# 3_3_buck.net
KiCad netlist of a schematic drawn in Altium Designer
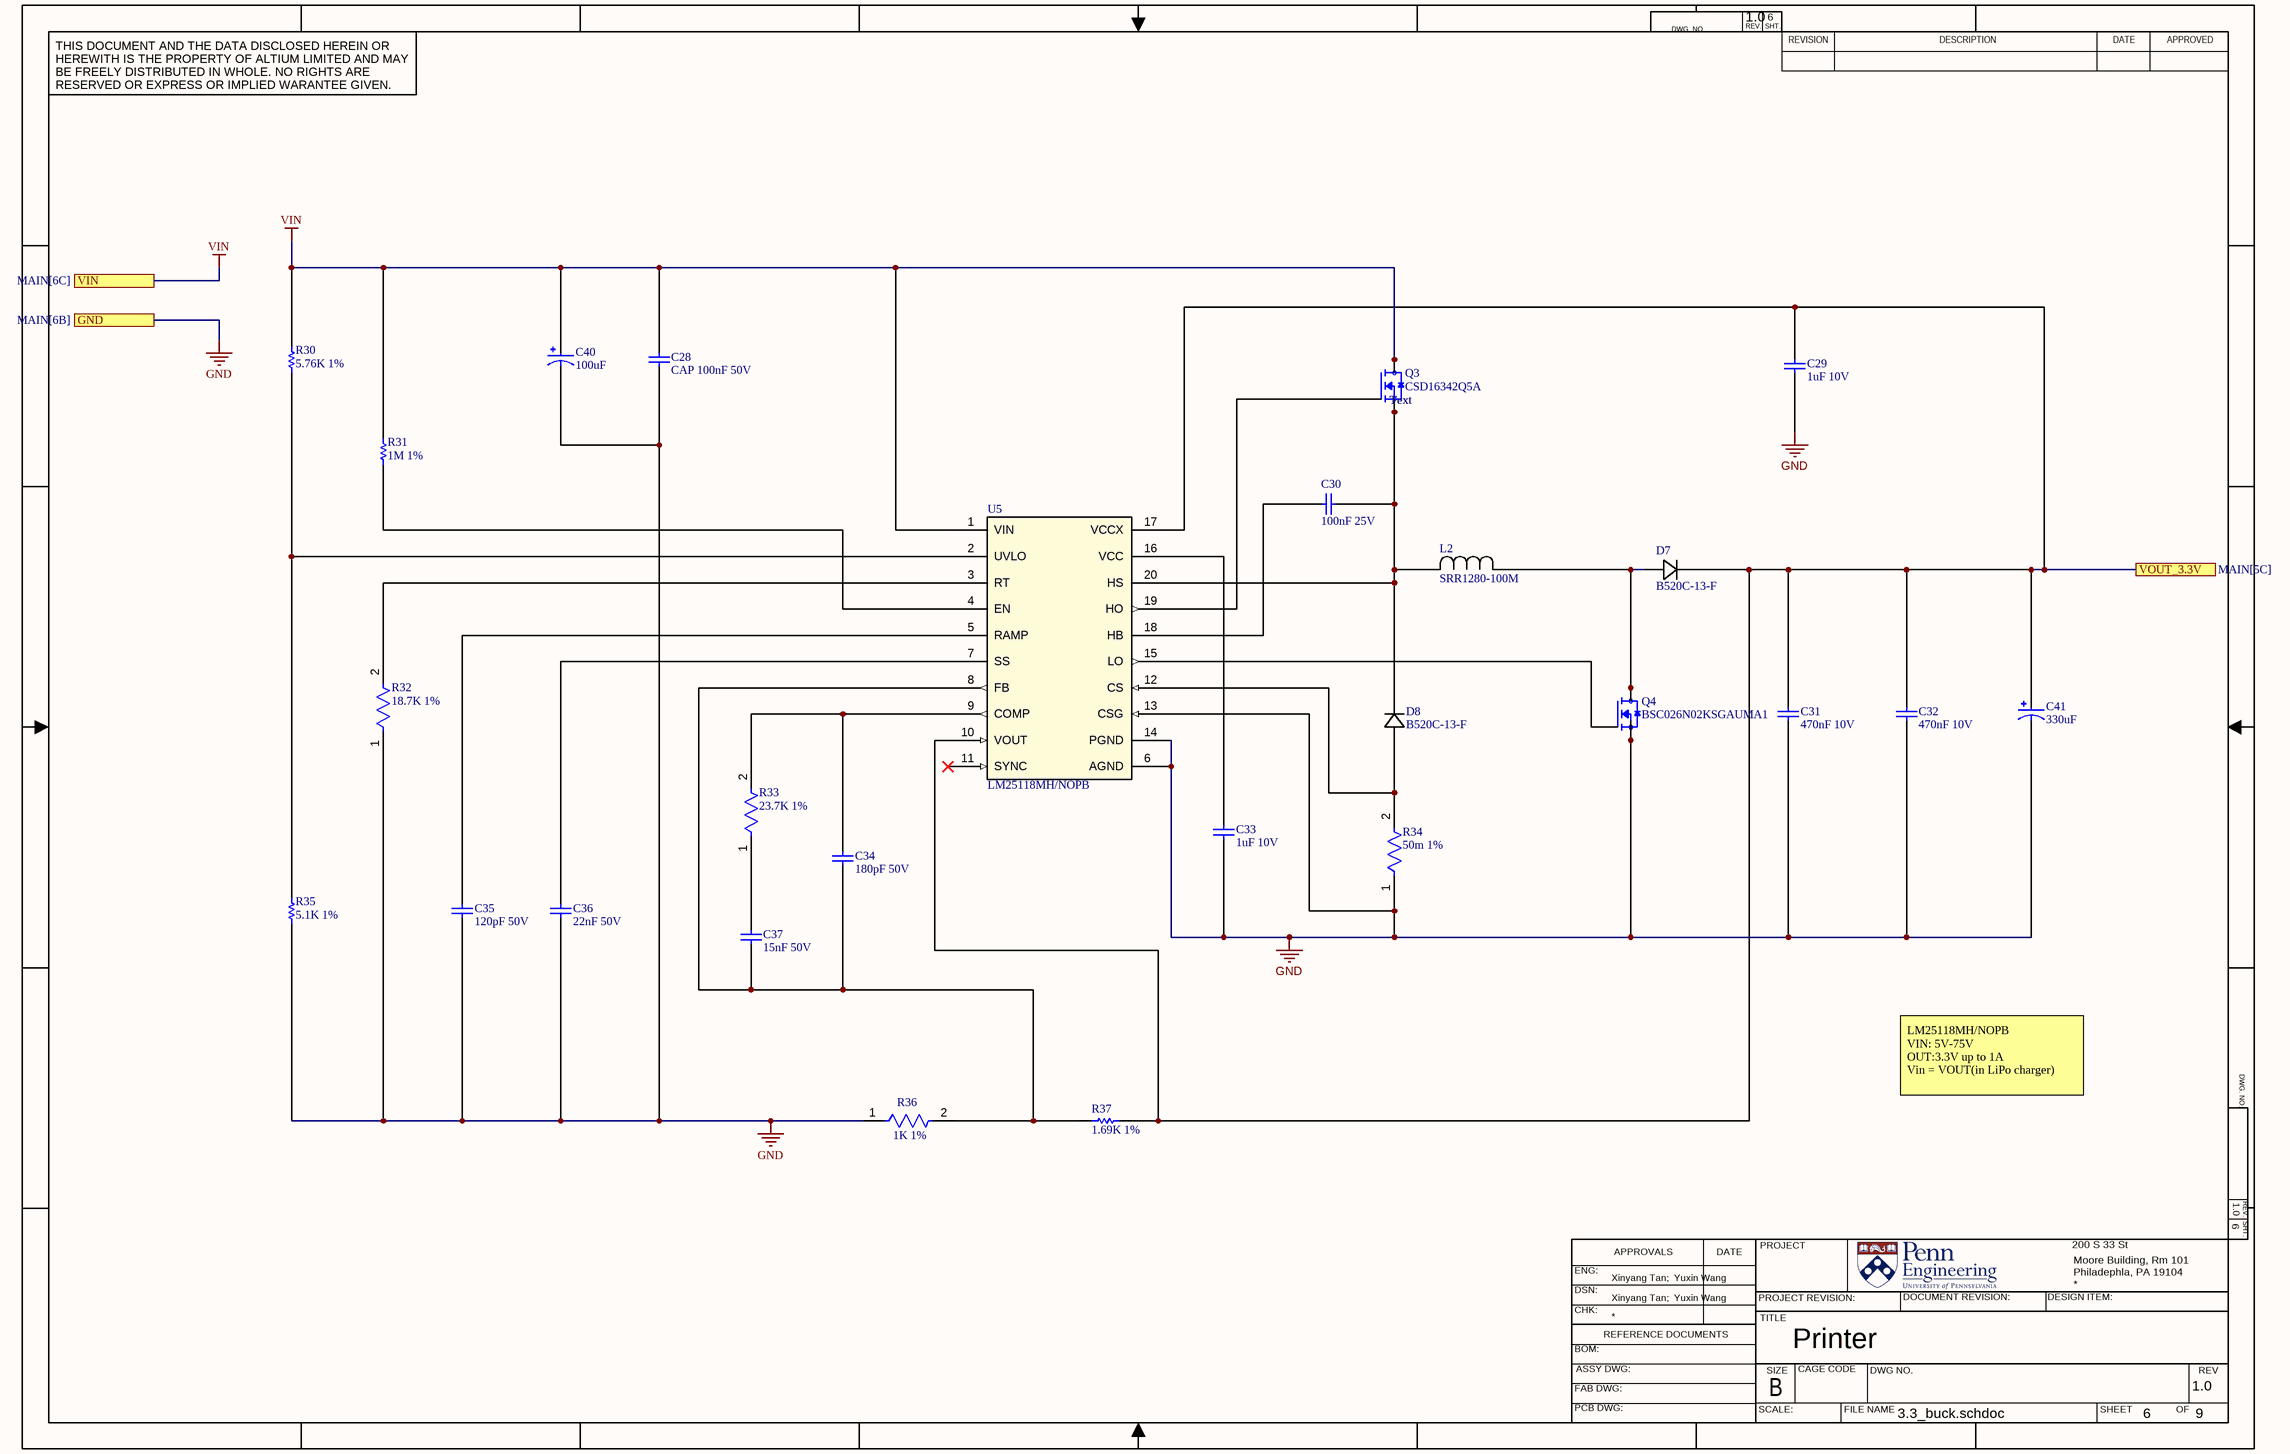
[diagram p0: 3.3_buck.schdoc]

(export (version "E")
  (design (tool "Eeschema 10.0.6"))
  (components
    (comp (ref "C28")
      (value "CAP 100nF 50V")
      (footprint "CAPC0805(2012)100_L")
      (description "CAP 100nF 50V ±5% 0805 (2012 Metric) Thickness 1mm SMD")
      (fields (field (name "TOLERANCE") "Â±5%"))
      (libsource (lib "Altium Content Vault") (part "CAP"))
    )
    (comp (ref "C29")
      (value "1uF 10V")
      (footprint "CAPC1608X90X35ML15T15")
      (fields (field (name "MANUFACTURER") "Kemet") (field (name "PART NUMBER") "C0603C105K8RACTU"))
      (libsource (lib "Altium Content Vault") (part "CAP"))
    )
    (comp (ref "C30")
      (value "100nF 25V")
      (footprint "CAPC0805(2012)75_M")
      (description "CAP 100nF 25V ±20% 0805 (2012 Metric) Thickness 0.75mm SMD")
      (fields (field (name "TOLERANCE") "Â±20%"))
      (libsource (lib "Altium Content Vault") (part "CAP"))
    )
    (comp (ref "C31")
      (value "470nF 10V")
      (footprint "CAPC0402(1005)60_M")
      (description "CAP 470nF 10V -20% to +80% 0402 (1005 Metric) Thickness 0.6mm SMD")
      (fields (field (name "TOLERANCE") "-20% to +80%"))
      (libsource (lib "Altium Content Vault") (part "CAP"))
    )
    (comp (ref "C32")
      (value "470nF 10V")
      (footprint "CAPC0402(1005)60_M")
      (description "CAP 470nF 10V -20% to +80% 0402 (1005 Metric) Thickness 0.6mm SMD")
      (fields (field (name "TOLERANCE") "-20% to +80%"))
      (libsource (lib "Altium Content Vault") (part "CAP"))
    )
    (comp (ref "C33")
      (value "1uF 10V")
      (footprint "CAPC1608X90X35ML15T15")
      (fields (field (name "MANUFACTURER") "Kemet") (field (name "PART NUMBER") "C0603C105K8RACTU"))
      (libsource (lib "Altium Content Vault") (part "CAP"))
    )
    (comp (ref "C34")
      (value "180pF 50V")
      (footprint "CAPC0805(2012)100_L")
      (description "CAP 180pF 50V ±20% 0805 (2012 Metric) Thickness 1mm SMD")
      (fields (field (name "TOLERANCE") "Â±20%"))
      (libsource (lib "Altium Content Vault") (part "CAP"))
    )
    (comp (ref "C35")
      (value "120pF 50V")
      (footprint "CAPC0805(2012)75_L")
      (description "CAP 120pF 50V ±10% 0805 (2012 Metric) Thickness 0.75mm SMD")
      (fields (field (name "TOLERANCE") "Â±10%"))
      (libsource (lib "Altium Content Vault") (part "CAP"))
    )
    (comp (ref "C36")
      (value "22nF 50V")
      (footprint "CAPC0805(2012)75_N")
      (description "CAP 22nF 50V ±20% 0805 (2012 Metric) Thickness 0.75mm SMD")
      (fields (field (name "TOLERANCE") "Â±20%"))
      (libsource (lib "Altium Content Vault") (part "CAP"))
    )
    (comp (ref "C37")
      (value "15nF 50V")
      (footprint "CAPC0805(2012)75_N")
      (description "CAP 15nF 50V ±20% 0805 (2012 Metric) Thickness 0.75mm SMD")
      (fields (field (name "TOLERANCE") "Â±20%"))
      (libsource (lib "Altium Content Vault") (part "CAP"))
    )
    (comp (ref "C40")
      (value "100uF")
      (footprint "CAP_593D-D_VSS")
      (description "No Description Available")
      (fields
        (field (name "MANUFACTURER_PART_NUMBER") "593D107X0010D2TE3")
        (field (name "COPYRIGHT") "Copyright (C) 2022 Ultra Librarian. All rights reserved.")
      )
      (libsource (lib "Schematics") (part "593D107X0010D2TE3"))
    )
    (comp (ref "C41")
      (value "330uF")
      (footprint "CHEMI-F80")
      (description "No Description Available")
      (fields
        (field (name "MANUFACTURER_PART_NUMBER") "APXE6R3ARA331MF80G")
        (field (name "COPYRIGHT") "Copyright (C) 2022 Ultra Librarian. All rights reserved.")
      )
      (libsource (lib "Schematics") (part "APXE6R3ARA331MF80G"))
    )
    (comp (ref "D7")
      (value "B520C-13-F")
      (footprint "SMC_DIO")
      (description "No Description Available")
      (fields (field (name "COPYRIGHT") "Copyright (C) 2022 Ultra Librarian. All rights reserved."))
      (libsource (lib "Schematics") (part "B520C-13-F"))
    )
    (comp (ref "D8")
      (value "B520C-13-F")
      (footprint "SMC_DIO")
      (description "No Description Available")
      (fields (field (name "COPYRIGHT") "Copyright (C) 2022 Ultra Librarian. All rights reserved."))
      (libsource (lib "Schematics") (part "B520C-13-F"))
    )
    (comp (ref "L2")
      (value "SRR1280-100M")
      (footprint "IND_BOURNS_SRR1280")
      (description "No Description Available")
      (fields (field (name "COPYRIGHT") "Copyright (C) 2022 Ultra Librarian. All rights reserved."))
      (libsource (lib "Schematics") (part "SRR1280-100M"))
    )
    (comp (ref "Q3")
      (value "CSD16342Q5A")
      (footprint "DQJ8_TEX")
      (description "No Description Available")
      (fields (field (name "COPYRIGHT") "Copyright (C) 2022 Ultra Librarian. All rights reserved."))
      (libsource (lib "Schematics") (part "CSD16342Q5A"))
    )
    (comp (ref "Q4")
      (value "BSC026N02KSGAUMA1")
      (footprint "PG-TDSON-8_BSC026N02KSGAUMA1_INF")
      (description "No Description Available")
      (fields (field (name "COPYRIGHT") "Copyright (C) 2022 Ultra Librarian. All rights reserved."))
      (libsource (lib "Schematics") (part "BSC026N02KSGAUMA1"))
    )
    (comp (ref "R30")
      (value "5.76K 1%")
      (footprint "RESC1608X55X25ML10T15")
      (fields (field (name "PART NUMBER") "RC0603FR-075K76L") (field (name "MANUFACTURER") "Yageo"))
      (libsource (lib "Altium Content Vault") (part "RES"))
    )
    (comp (ref "R31")
      (value "1M 1%")
      (footprint "RESC1608X55X25LL10T15")
      (description "Chip Resistor, 1 MOhm, +/- 1%, 100 mW, -55 to 155 degC, 0603 (1608 Metric), RoHS, Tape and Reel")
      (fields (field (name "TOLERANCE") "20%"))
      (libsource (lib "Altium Content Vault") (part "RES-2"))
    )
    (comp (ref "R32")
      (value "18.7K 1%")
      (footprint "FP-RT0805-MFG")
      (description "RES SMD 18.7K OHM 1% 1/8W 0805")
      (fields
        (field (name "OCTOPART") "https://octopart.com/rt0805fre0718k7l-yageo-1462871")
        (field (name "TOLERANCE") "0.0001")
      )
      (libsource (lib "Altium Content Vault") (part "1029c3af85768c4190bb7ad29bc67b5"))
    )
    (comp (ref "R33")
      (value "23.7K 1%")
      (footprint "FP-AC0402-MFG")
      (description "RES SMD 23.7K OHM 1% 1/16W 0402")
      (fields
        (field (name "OCTOPART") "https://octopart.com/ac0402fr-0723k7l-yageo-71366670")
        (field (name "MANUFACTURER PART NUMBER") "AC0402FR-0723K7L")
      )
      (libsource (lib "Altium Content Vault") (part "1029c3af85768c4190bb7ad29bc67b5"))
    )
    (comp (ref "R34")
      (value "50m 1%")
      (footprint "FP-CSR1206-IPC_A")
      (description "General Purpose Thick Film Chip Resistor, 1206, 50mΩ, 1%, 100ppm/°C, 0.5W")
      (fields (field (name "TOLERANCE") "1%"))
      (libsource (lib "Altium Content Vault") (part "1029c3af85768c4190bb7ad29bc67b5"))
    )
    (comp (ref "R35")
      (value "5.1K 1%")
      (footprint "RESC1608X55X25ML10T15")
      (fields (field (name "MANUFACTURER") "Yageo") (field (name "PART NUMBER") "RC0603FR-075K1L"))
      (libsource (lib "Altium Content Vault") (part "RES"))
    )
    (comp (ref "R36")
      (value "1K 1%")
      (footprint "FP-RC0603-0_55-IPC_C")
      (description "RES 1K OHM 1% 1/10W 0603")
      (fields (field (name "TOLERANCE") "1%"))
      (libsource (lib "Altium Content Vault") (part "1029c3af85768c4190bb7ad29bc67b5"))
    )
    (comp (ref "R37")
      (value "1.69K 1%")
      (footprint "RESC1608X55X25NL10T15")
      (fields (field (name "MANUFACTURER") "Yageo") (field (name "PART NUMBER") "RC0603FR-071K69L"))
      (libsource (lib "Altium Content Vault") (part "RES"))
    )
    (comp (ref "U5")
      (value "LM25118MH/NOPB")
      (footprint "MXA20A")
      (description "No Description Available")
      (fields (field (name "COPYRIGHT") "Copyright (C) 2022 Ultra Librarian. All rights reserved."))
      (libsource (lib "Schematics") (part "LM25118MH/NOPB"))
    )
  )
  (nets
    (net (code "1") (name "/VOUT_3.3V") (class "Default")
      (node (ref "C29") (pin "2") (pinfunction "2_2") (pintype "passive"))
      (node (ref "C31") (pin "2") (pinfunction "2_2") (pintype "passive"))
      (node (ref "C32") (pin "2") (pinfunction "2_2") (pintype "passive"))
      (node (ref "C41") (pin "1") (pinfunction "1_1") (pintype "passive"))
      (node (ref "D7") (pin "1") (pinfunction "1_1") (pintype "passive"))
      (node (ref "R37") (pin "2") (pinfunction "2_2") (pintype "passive"))
      (node (ref "U5") (pin "10") (pinfunction "VOUT_10") (pintype "input"))
      (node (ref "U5") (pin "17") (pinfunction "VCCX_17") (pintype "power_in"))
    )
    (net (code "2") (name "GND") (class "Default")
      (node (ref "C28") (pin "1") (pinfunction "1_1") (pintype "passive"))
      (node (ref "C29") (pin "1") (pinfunction "1_1") (pintype "passive"))
      (node (ref "C31") (pin "1") (pinfunction "1_1") (pintype "passive"))
      (node (ref "C32") (pin "1") (pinfunction "1_1") (pintype "passive"))
      (node (ref "C33") (pin "1") (pinfunction "1_1") (pintype "passive"))
      (node (ref "C35") (pin "1") (pinfunction "1_1") (pintype "passive"))
      (node (ref "C36") (pin "1") (pinfunction "1_1") (pintype "passive"))
      (node (ref "C40") (pin "2") (pinfunction "2_2") (pintype "passive"))
      (node (ref "C41") (pin "2") (pinfunction "2_2") (pintype "passive"))
      (node (ref "Q4") (pin "2") (pinfunction "S_2") (pintype "passive"))
      (node (ref "Q4") (pin "3") (pinfunction "S_3") (pintype "passive"))
      (node (ref "R32") (pin "1") (pinfunction "1_1") (pintype "passive"))
      (node (ref "R34") (pin "1") (pinfunction "1_1") (pintype "passive"))
      (node (ref "R35") (pin "1") (pinfunction "1_1") (pintype "passive"))
      (node (ref "R36") (pin "1") (pinfunction "1_1") (pintype "passive"))
      (node (ref "U5") (pin "13") (pinfunction "CSG_13") (pintype "input"))
      (node (ref "U5") (pin "14") (pinfunction "PGND_14") (pintype "power_in"))
      (node (ref "U5") (pin "6") (pinfunction "AGND_6") (pintype "power_in"))
    )
    (net (code "3") (name "Net-(C37-Pad2)") (class "Default")
      (node (ref "C37") (pin "2") (pinfunction "2_2") (pintype "passive"))
      (node (ref "R33") (pin "1") (pinfunction "1_1") (pintype "passive"))
    )
    (net (code "4") (name "Net-(D7-Pad2)") (class "Default")
      (node (ref "D7") (pin "2") (pinfunction "2_2") (pintype "passive"))
      (node (ref "L2") (pin "1") (pinfunction "1_1") (pintype "passive"))
      (node (ref "Q4") (pin "5") (pinfunction "D_5") (pintype "passive"))
      (node (ref "Q4") (pin "6") (pinfunction "D_6") (pintype "passive"))
      (node (ref "Q4") (pin "7") (pinfunction "D_7") (pintype "passive"))
      (node (ref "Q4") (pin "8") (pinfunction "D_8") (pintype "passive"))
    )
    (net (code "5") (name "Net-(Q3-G)") (class "Default")
      (node (ref "Q3") (pin "4") (pinfunction "G_4") (pintype "passive"))
      (node (ref "U5") (pin "19") (pinfunction "HO_19") (pintype "output"))
    )
    (net (code "6") (name "Net-(Q4-G)") (class "Default")
      (node (ref "Q4") (pin "4") (pinfunction "G_4") (pintype "passive"))
      (node (ref "U5") (pin "15") (pinfunction "LO_15") (pintype "output"))
    )
    (net (code "7") (name "Net-(U5-COMP)") (class "Default")
      (node (ref "C34") (pin "2") (pinfunction "2_2") (pintype "passive"))
      (node (ref "R33") (pin "2") (pinfunction "2_2") (pintype "passive"))
      (node (ref "U5") (pin "9") (pinfunction "COMP_9") (pintype "output"))
    )
    (net (code "8") (name "Net-(U5-CS)") (class "Default")
      (node (ref "D8") (pin "2") (pinfunction "2_2") (pintype "passive"))
      (node (ref "R34") (pin "2") (pinfunction "2_2") (pintype "passive"))
      (node (ref "U5") (pin "12") (pinfunction "CS_12") (pintype "input"))
    )
    (net (code "9") (name "Net-(U5-EN)") (class "Default")
      (node (ref "R31") (pin "1") (pinfunction "1_1") (pintype "passive"))
      (node (ref "U5") (pin "4") (pinfunction "EN_4") (pintype "passive"))
    )
    (net (code "10") (name "Net-(U5-FB)") (class "Default")
      (node (ref "C34") (pin "1") (pinfunction "1_1") (pintype "passive"))
      (node (ref "C37") (pin "1") (pinfunction "1_1") (pintype "passive"))
      (node (ref "R36") (pin "2") (pinfunction "2_2") (pintype "passive"))
      (node (ref "R37") (pin "1") (pinfunction "1_1") (pintype "passive"))
      (node (ref "U5") (pin "8") (pinfunction "FB_8") (pintype "output"))
    )
    (net (code "11") (name "Net-(U5-HB)") (class "Default")
      (node (ref "C30") (pin "1") (pinfunction "1_1") (pintype "passive"))
      (node (ref "U5") (pin "18") (pinfunction "HB_18") (pintype "passive"))
    )
    (net (code "12") (name "Net-(U5-HS)") (class "Default")
      (node (ref "C30") (pin "2") (pinfunction "2_2") (pintype "passive"))
      (node (ref "D8") (pin "1") (pinfunction "1_1") (pintype "passive"))
      (node (ref "L2") (pin "2") (pinfunction "2_2") (pintype "passive"))
      (node (ref "Q3") (pin "1") (pinfunction "S_1") (pintype "passive"))
      (node (ref "Q3") (pin "2") (pinfunction "S_2") (pintype "passive"))
      (node (ref "Q3") (pin "3") (pinfunction "S_3") (pintype "passive"))
      (node (ref "U5") (pin "20") (pinfunction "HS_20") (pintype "passive"))
    )
    (net (code "13") (name "Net-(U5-RAMP)") (class "Default")
      (node (ref "C35") (pin "2") (pinfunction "2_2") (pintype "passive"))
      (node (ref "U5") (pin "5") (pinfunction "RAMP_5") (pintype "passive"))
    )
    (net (code "14") (name "Net-(U5-RT)") (class "Default")
      (node (ref "R32") (pin "2") (pinfunction "2_2") (pintype "passive"))
      (node (ref "U5") (pin "3") (pinfunction "RT_3") (pintype "passive"))
    )
    (net (code "15") (name "Net-(U5-SS)") (class "Default")
      (node (ref "C36") (pin "2") (pinfunction "2_2") (pintype "passive"))
      (node (ref "U5") (pin "7") (pinfunction "SS_7") (pintype "passive"))
    )
    (net (code "16") (name "Net-(U5-UVLO)") (class "Default")
      (node (ref "R30") (pin "1") (pinfunction "1_1") (pintype "passive"))
      (node (ref "R35") (pin "2") (pinfunction "2_2") (pintype "passive"))
      (node (ref "U5") (pin "2") (pinfunction "UVLO_2") (pintype "passive"))
    )
    (net (code "17") (name "Net-(U5-VCC)") (class "Default")
      (node (ref "C33") (pin "2") (pinfunction "2_2") (pintype "passive"))
      (node (ref "U5") (pin "16") (pinfunction "VCC_16") (pintype "power_in"))
    )
    (net (code "18") (name "VIN") (class "Default")
      (node (ref "C28") (pin "2") (pinfunction "2_2") (pintype "passive"))
      (node (ref "C40") (pin "1") (pinfunction "1_1") (pintype "passive"))
      (node (ref "Q3") (pin "5") (pinfunction "D_5") (pintype "passive"))
      (node (ref "Q3") (pin "6") (pinfunction "D_6") (pintype "passive"))
      (node (ref "Q3") (pin "7") (pinfunction "D_7") (pintype "passive"))
      (node (ref "Q3") (pin "8") (pinfunction "D_8") (pintype "passive"))
      (node (ref "R30") (pin "2") (pinfunction "2_2") (pintype "passive"))
      (node (ref "R31") (pin "2") (pinfunction "2_2") (pintype "passive"))
      (node (ref "U5") (pin "1") (pinfunction "VIN_1") (pintype "power_in"))
    )
    (net (code "19") (name "unconnected-(Q4-S-Pad1)") (class "Default")
      (node (ref "Q4") (pin "1") (pinfunction "S_1") (pintype "passive"))
    )
    (net (code "20") (name "unconnected-(U5-SYNC-Pad11)") (class "Default")
      (node (ref "U5") (pin "11") (pinfunction "SYNC_11") (pintype "input+no_connect"))
    )
  )
)
